# USB_UART_V1_4_1.net
KiCad netlist of a schematic drawn in Altium Designer
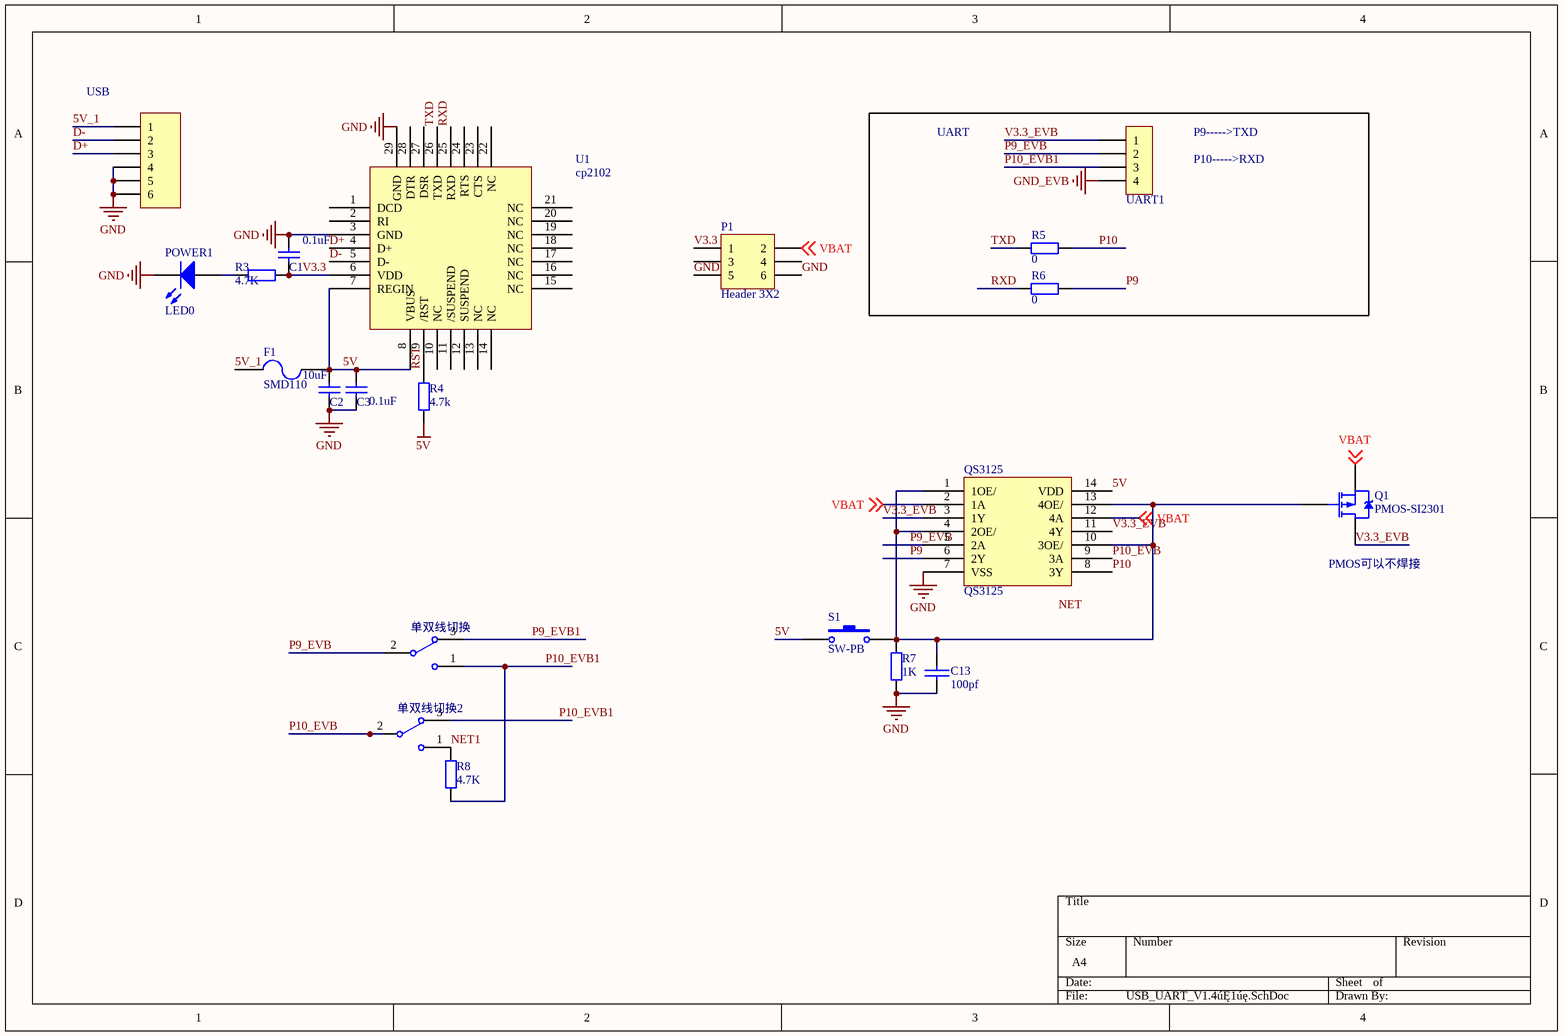
[diagram p0: USB_UART_V1.4úĘ1úę.SchDoc]

(export (version "E")
  (design (tool "Eeschema 10.0.6"))
  (components
    (comp (ref "C1")
      (value "0.1uF")
      (footprint "C0603")
      (description "Capacitor")
      (fields (field (name "PUBLISHER") "Altium Limited"))
      (libsource (lib "Miscellaneous Devices") (part "Cap"))
    )
    (comp (ref "C2")
      (value "10uF")
      (footprint "C0603")
      (description "Capacitor")
      (fields (field (name "PUBLISHER") "Altium Limited"))
      (libsource (lib "Miscellaneous Devices") (part "Cap"))
    )
    (comp (ref "C3")
      (value "0.1uF")
      (footprint "C0603")
      (description "Capacitor")
      (fields (field (name "PUBLISHER") "Altium Limited"))
      (libsource (lib "Miscellaneous Devices") (part "Cap"))
    )
    (comp (ref "C13") (value "100pf") (footprint "C0603") (libsource (lib "PCB_Project") (part "电容瓷片")))
    (comp (ref "F1")
      (value "SMD110")
      (footprint "1812")
      (description "Fuse")
      (libsource (lib "RC-sheet") (part "FUSE2"))
    )
    (comp (ref "P1")
      (value "Header 3X2")
      (footprint "HDR2X3")
      (description "Header, 3-Pin, Dual row")
      (fields (field (name "PUBLISHER") "Altium Limited"))
      (libsource (lib "Miscellaneous Connectors") (part "Header 3X2"))
    )
    (comp (ref "POWER1")
      (value "LED0")
      (footprint "LED0603")
      (description "Typical INFRARED GaAs LED")
      (fields (field (name "PUBLISHER") "Altium Limited"))
      (libsource (lib "Miscellaneous Devices") (part "LED0"))
    )
    (comp (ref "Q1")
      (value "PMOS-SI2301")
      (footprint "Pmos si2301")
      (description "P-Channel Power MOSFET")
      (fields (field (name "PUBLISHER") "Altium Limited"))
      (libsource (lib "Miscellaneous Devices") (part "PMOS-2"))
    )
    (comp (ref "QS3125") (value "QS3125") (libsource (lib "Phyplus") (part "QS3125")))
    (comp (ref "R3")
      (value "4.7K")
      (footprint "C0603")
      (description "Resistor")
      (fields (field (name "PUBLISHER") "Altium Limited"))
      (libsource (lib "") (part "Res2_2"))
    )
    (comp (ref "R4")
      (value "4.7k")
      (footprint "C0603")
      (description "Resistor")
      (fields (field (name "PUBLISHER") "Altium Limited"))
      (libsource (lib "Miscellaneous Devices") (part "Res2"))
    )
    (comp (ref "R5")
      (value "0")
      (footprint "C0603")
      (description "Resistor")
      (fields (field (name "Comment") "4.7k") (field (name "PUBLISHER") "Altium Limited"))
      (libsource (lib "") (part "Res2_3"))
    )
    (comp (ref "R6")
      (value "0")
      (footprint "C0603")
      (description "Resistor")
      (fields (field (name "Comment") "4.7k") (field (name "PUBLISHER") "Altium Limited"))
      (libsource (lib "") (part "Res2_2"))
    )
    (comp (ref "R7")
      (value "1K")
      (footprint "C0603")
      (description "Resistor")
      (fields (field (name "Comment") "4.7k") (field (name "PUBLISHER") "Altium Limited"))
      (libsource (lib "") (part "Res2_1"))
    )
    (comp (ref "R8")
      (value "4.7K")
      (footprint "C0603")
      (description "Resistor")
      (fields (field (name "Comment") "4.7k") (field (name "PUBLISHER") "Altium Limited"))
      (libsource (lib "") (part "Res2_1"))
    )
    (comp (ref "S1")
      (value "SW-PB")
      (footprint "SPST-2")
      (description "Switch")
      (fields (field (name "PUBLISHER") "Altium Limited"))
      (libsource (lib "Miscellaneous Devices") (part "SW-PB"))
    )
    (comp (ref "U1") (value "cp2102") (footprint "CP2102") (libsource (lib "Phyplus") (part "cp2102")))
    (comp (ref "UART1") (value "CON4") (footprint "HDR1X4") (libsource (lib "RF_0603") (part "CON4")))
    (comp (ref "USB")
      (value "MHDR1X6")
      (footprint "USB 公口")
      (description "Header, 6-Pin")
      (fields (field (name "PUBLISHER") "Altium Limited"))
      (libsource (lib "Miscellaneous Connectors") (part "MHDR1X6"))
    )
    (comp (ref "单双线切换")
      (value "SW-SPDT")
      (footprint "HDR1X3")
      (description "SPDT Subminiature Toggle Switch, Right Angle Mounting, Vertical Actuation")
      (fields (field (name "PUBLISHER") "Altium Limited"))
      (libsource (lib "Miscellaneous Devices") (part "SW-SPDT"))
    )
    (comp (ref "单双线切换2")
      (value "SW-SPDT")
      (footprint "HDR1X3")
      (description "SPDT Subminiature Toggle Switch, Right Angle Mounting, Vertical Actuation")
      (fields (field (name "PUBLISHER") "Altium Limited"))
      (libsource (lib "Miscellaneous Devices") (part "SW-SPDT"))
    )
  )
  (nets
    (net (code "1") (name "/5V_1") (class "Default")
      (node (ref "F1") (pin "2") (pinfunction "2_2") (pintype "passive"))
      (node (ref "USB") (pin "1") (pinfunction "1_1") (pintype "passive"))
    )
    (net (code "2") (name "/D+") (class "Default")
      (node (ref "U1") (pin "4") (pinfunction "D+_4") (pintype "passive"))
      (node (ref "USB") (pin "3") (pinfunction "3_3") (pintype "passive"))
    )
    (net (code "3") (name "/D-") (class "Default")
      (node (ref "U1") (pin "5") (pinfunction "D-_5") (pintype "passive"))
      (node (ref "USB") (pin "2") (pinfunction "2_2") (pintype "passive"))
    )
    (net (code "5") (name "/NET1") (class "Default")
      (node (ref "R8") (pin "1") (pinfunction "1_1") (pintype "passive"))
      (node (ref "单双线切换2") (pin "1") (pinfunction "1_1") (pintype "passive"))
    )
    (net (code "6") (name "/P9") (class "Default")
      (node (ref "QS3125") (pin "6") (pinfunction "2Y_6") (pintype "passive"))
      (node (ref "R6") (pin "2") (pinfunction "2_2") (pintype "passive"))
    )
    (net (code "7") (name "/P9_EVB") (class "Default")
      (node (ref "QS3125") (pin "5") (pinfunction "2A_5") (pintype "passive"))
      (node (ref "UART1") (pin "2") (pinfunction "2_2") (pintype "passive"))
      (node (ref "单双线切换") (pin "2") (pinfunction "2_2") (pintype "passive"))
    )
    (net (code "8") (name "/P9_EVB1") (class "Default")
      (node (ref "单双线切换") (pin "3") (pinfunction "3_3") (pintype "passive"))
    )
    (net (code "9") (name "/P10") (class "Default")
      (node (ref "QS3125") (pin "8") (pinfunction "3Y_8") (pintype "passive"))
      (node (ref "R5") (pin "1") (pinfunction "1_1") (pintype "passive"))
    )
    (net (code "10") (name "/P10_EVB") (class "Default")
      (node (ref "QS3125") (pin "9") (pinfunction "3A_9") (pintype "passive"))
      (node (ref "单双线切换2") (pin "2") (pinfunction "2_2") (pintype "passive"))
    )
    (net (code "11") (name "/P10_EVB1") (class "Default")
      (node (ref "R8") (pin "2") (pinfunction "2_2") (pintype "passive"))
      (node (ref "UART1") (pin "3") (pinfunction "3_3") (pintype "passive"))
      (node (ref "单双线切换") (pin "1") (pinfunction "1_1") (pintype "passive"))
      (node (ref "单双线切换2") (pin "3") (pinfunction "3_3") (pintype "passive"))
    )
    (net (code "12") (name "/RST") (class "Default")
      (node (ref "R4") (pin "2") (pinfunction "2_2") (pintype "passive"))
      (node (ref "U1") (pin "9") (pinfunction "/RST_9") (pintype "passive"))
    )
    (net (code "13") (name "/RXD") (class "Default")
      (node (ref "R6") (pin "1") (pinfunction "1_1") (pintype "passive"))
      (node (ref "U1") (pin "25") (pinfunction "RXD_25") (pintype "passive"))
    )
    (net (code "14") (name "/TXD") (class "Default")
      (node (ref "R5") (pin "2") (pinfunction "2_2") (pintype "passive"))
      (node (ref "U1") (pin "26") (pinfunction "TXD_26") (pintype "passive"))
    )
    (net (code "15") (name "/V3.3") (class "Default")
      (node (ref "C1") (pin "1") (pinfunction "1_1") (pintype "passive"))
      (node (ref "P1") (pin "1") (pinfunction "1_1") (pintype "passive"))
      (node (ref "R3") (pin "2") (pinfunction "2_2") (pintype "passive"))
      (node (ref "U1") (pin "6") (pinfunction "VDD_6") (pintype "passive"))
    )
    (net (code "16") (name "/V3.3_EVB") (class "Default")
      (node (ref "Q1") (pin "2") (pinfunction "D_2") (pintype "passive"))
      (node (ref "QS3125") (pin "11") (pinfunction "4Y_11") (pintype "passive"))
      (node (ref "QS3125") (pin "3") (pinfunction "1Y_3") (pintype "passive"))
      (node (ref "UART1") (pin "1") (pinfunction "1_1") (pintype "passive"))
    )
    (net (code "17") (name "5V") (class "Default")
      (node (ref "C2") (pin "2") (pinfunction "2_2") (pintype "passive"))
      (node (ref "C3") (pin "2") (pinfunction "2_2") (pintype "passive"))
      (node (ref "F1") (pin "1") (pinfunction "1_1") (pintype "passive"))
      (node (ref "QS3125") (pin "14") (pinfunction "VDD_14") (pintype "passive"))
      (node (ref "R4") (pin "1") (pinfunction "1_1") (pintype "passive"))
      (node (ref "S1") (pin "1") (pinfunction "1_1") (pintype "passive"))
      (node (ref "U1") (pin "7") (pinfunction "REGIN_7") (pintype "passive"))
      (node (ref "U1") (pin "8") (pinfunction "VBUS_8") (pintype "passive"))
    )
    (net (code "18") (name "GND") (class "Default")
      (node (ref "C1") (pin "2") (pinfunction "2_2") (pintype "passive"))
      (node (ref "C13") (pin "2") (pinfunction "2_2") (pintype "passive"))
      (node (ref "C2") (pin "1") (pinfunction "1_1") (pintype "passive"))
      (node (ref "C3") (pin "1") (pinfunction "1_1") (pintype "passive"))
      (node (ref "P1") (pin "5") (pinfunction "5_5") (pintype "passive"))
      (node (ref "P1") (pin "6") (pinfunction "6_6") (pintype "passive"))
      (node (ref "POWER1") (pin "2") (pinfunction "K_2") (pintype "passive"))
      (node (ref "QS3125") (pin "7") (pinfunction "VSS_7") (pintype "passive"))
      (node (ref "R7") (pin "2") (pinfunction "2_2") (pintype "passive"))
      (node (ref "U1") (pin "29") (pinfunction "GND_29") (pintype "passive"))
      (node (ref "U1") (pin "3") (pinfunction "GND_3") (pintype "passive"))
      (node (ref "USB") (pin "4") (pinfunction "4_4") (pintype "passive"))
      (node (ref "USB") (pin "5") (pinfunction "5_5") (pintype "passive"))
      (node (ref "USB") (pin "6") (pinfunction "6_6") (pintype "passive"))
    )
    (net (code "19") (name "GND_EVB") (class "Default")
      (node (ref "UART1") (pin "4") (pinfunction "4_4") (pintype "passive"))
    )
    (net (code "20") (name "Net-(POWER1-A)") (class "Default")
      (node (ref "POWER1") (pin "1") (pinfunction "A_1") (pintype "passive"))
      (node (ref "R3") (pin "1") (pinfunction "1_1") (pintype "passive"))
    )
    (net (code "21") (name "Net-(Q1-G)") (class "Default")
      (node (ref "C13") (pin "1") (pinfunction "1_1") (pintype "passive"))
      (node (ref "Q1") (pin "1") (pinfunction "G_1") (pintype "passive"))
      (node (ref "QS3125") (pin "1") (pinfunction "1OE/_1") (pintype "passive"))
      (node (ref "QS3125") (pin "10") (pinfunction "3OE/_10") (pintype "passive"))
      (node (ref "QS3125") (pin "13") (pinfunction "4OE/_13") (pintype "passive"))
      (node (ref "QS3125") (pin "4") (pinfunction "2OE/_4") (pintype "passive"))
      (node (ref "R7") (pin "1") (pinfunction "1_1") (pintype "passive"))
      (node (ref "S1") (pin "2") (pinfunction "2_2") (pintype "passive"))
    )
    (net (code "22") (name "VBAT") (class "Default")
      (node (ref "P1") (pin "2") (pinfunction "2_2") (pintype "passive"))
      (node (ref "Q1") (pin "3") (pinfunction "S_3") (pintype "passive"))
      (node (ref "QS3125") (pin "12") (pinfunction "4A_12") (pintype "passive"))
      (node (ref "QS3125") (pin "2") (pinfunction "1A_2") (pintype "passive"))
    )
    (net (code "23") (name "unconnected-(P1-Pad3)") (class "Default")
      (node (ref "P1") (pin "3") (pinfunction "3_3") (pintype "passive"))
    )
    (net (code "24") (name "unconnected-(P1-Pad4)") (class "Default")
      (node (ref "P1") (pin "4") (pinfunction "4_4") (pintype "passive"))
    )
    (net (code "25") (name "unconnected-(U1-CTS-Pad23)") (class "Default")
      (node (ref "U1") (pin "23") (pinfunction "CTS_23") (pintype "passive"))
    )
    (net (code "26") (name "unconnected-(U1-DCD-Pad1)") (class "Default")
      (node (ref "U1") (pin "1") (pinfunction "DCD_1") (pintype "passive"))
    )
    (net (code "27") (name "unconnected-(U1-DSR-Pad27)") (class "Default")
      (node (ref "U1") (pin "27") (pinfunction "DSR_27") (pintype "passive"))
    )
    (net (code "28") (name "unconnected-(U1-DTR-Pad28)") (class "Default")
      (node (ref "U1") (pin "28") (pinfunction "DTR_28") (pintype "passive"))
    )
    (net (code "29") (name "unconnected-(U1-NC-Pad10)") (class "Default")
      (node (ref "U1") (pin "10") (pinfunction "NC_10") (pintype "passive"))
    )
    (net (code "30") (name "unconnected-(U1-NC-Pad13)") (class "Default")
      (node (ref "U1") (pin "13") (pinfunction "NC_13") (pintype "passive"))
    )
    (net (code "31") (name "unconnected-(U1-NC-Pad14)") (class "Default")
      (node (ref "U1") (pin "14") (pinfunction "NC_14") (pintype "passive"))
    )
    (net (code "32") (name "unconnected-(U1-NC-Pad15)") (class "Default")
      (node (ref "U1") (pin "15") (pinfunction "NC_15") (pintype "passive"))
    )
    (net (code "33") (name "unconnected-(U1-NC-Pad16)") (class "Default")
      (node (ref "U1") (pin "16") (pinfunction "NC_16") (pintype "passive"))
    )
    (net (code "34") (name "unconnected-(U1-NC-Pad17)") (class "Default")
      (node (ref "U1") (pin "17") (pinfunction "NC_17") (pintype "passive"))
    )
    (net (code "35") (name "unconnected-(U1-NC-Pad18)") (class "Default")
      (node (ref "U1") (pin "18") (pinfunction "NC_18") (pintype "passive"))
    )
    (net (code "36") (name "unconnected-(U1-NC-Pad19)") (class "Default")
      (node (ref "U1") (pin "19") (pinfunction "NC_19") (pintype "passive"))
    )
    (net (code "37") (name "unconnected-(U1-NC-Pad20)") (class "Default")
      (node (ref "U1") (pin "20") (pinfunction "NC_20") (pintype "passive"))
    )
    (net (code "38") (name "unconnected-(U1-NC-Pad21)") (class "Default")
      (node (ref "U1") (pin "21") (pinfunction "NC_21") (pintype "passive"))
    )
    (net (code "39") (name "unconnected-(U1-NC-Pad22)") (class "Default")
      (node (ref "U1") (pin "22") (pinfunction "NC_22") (pintype "passive"))
    )
    (net (code "40") (name "unconnected-(U1-RI-Pad2)") (class "Default")
      (node (ref "U1") (pin "2") (pinfunction "RI_2") (pintype "passive"))
    )
    (net (code "41") (name "unconnected-(U1-RTS-Pad24)") (class "Default")
      (node (ref "U1") (pin "24") (pinfunction "RTS_24") (pintype "passive"))
    )
    (net (code "42") (name "unconnected-(U1-SUSPEND-Pad12)") (class "Default")
      (node (ref "U1") (pin "12") (pinfunction "SUSPEND_12") (pintype "passive"))
    )
    (net (code "43") (name "unconnected-(U1-{slash}SUSPEND-Pad11)") (class "Default")
      (node (ref "U1") (pin "11") (pinfunction "/SUSPEND_11") (pintype "passive"))
    )
  )
)
